# senzor.net
KiCad netlist of a schematic drawn in Altium Designer
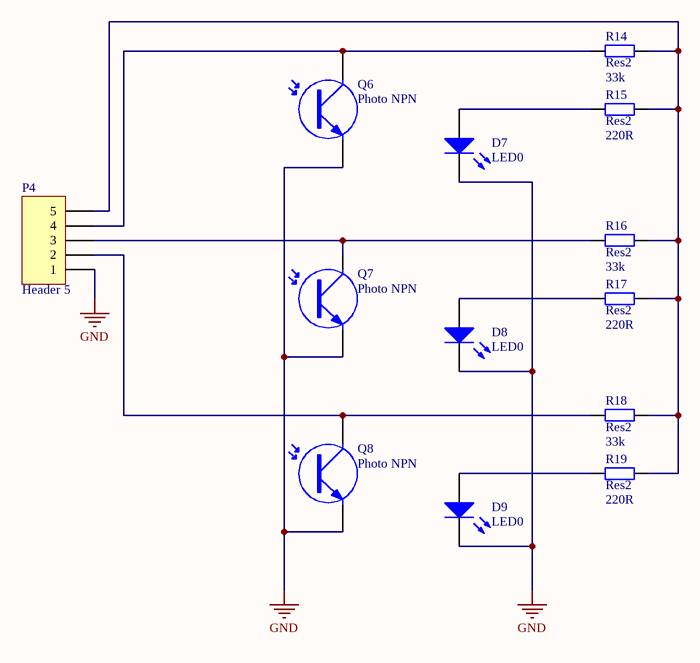
[diagram p0: senzor.SchDoc]

(export (version "E")
  (design (tool "Eeschema 10.0.6"))
  (components
    (comp (ref "D7")
      (value "LED0")
      (footprint "LED-0")
      (description "Typical INFRARED GaAs LED")
      (fields (field (name "PUBLISHER") "Altium Limited"))
      (libsource (lib "Miscellaneous Devices") (part "LED0"))
    )
    (comp (ref "D8")
      (value "LED0")
      (footprint "LED-0")
      (description "Typical INFRARED GaAs LED")
      (fields (field (name "PUBLISHER") "Altium Limited"))
      (libsource (lib "Miscellaneous Devices") (part "LED0"))
    )
    (comp (ref "D9")
      (value "LED0")
      (footprint "LED-0")
      (description "Typical INFRARED GaAs LED")
      (fields (field (name "PUBLISHER") "Altium Limited"))
      (libsource (lib "Miscellaneous Devices") (part "LED0"))
    )
    (comp (ref "P4")
      (value "Header 5")
      (footprint "HDR1X5")
      (description "Header, 5-Pin")
      (fields (field (name "PUBLISHER") "Altium Limited"))
      (libsource (lib "Miscellaneous Connectors") (part "Header 5"))
    )
    (comp (ref "Q6")
      (value "Photo NPN")
      (footprint "TO-220_A")
      (description "NPN Phototransistor")
      (fields (field (name "PUBLISHER") "Altium Limited"))
      (libsource (lib "Miscellaneous Devices") (part "Photo NPN"))
    )
    (comp (ref "Q7")
      (value "Photo NPN")
      (footprint "TO-220_A")
      (description "NPN Phototransistor")
      (fields (field (name "PUBLISHER") "Altium Limited"))
      (libsource (lib "Miscellaneous Devices") (part "Photo NPN"))
    )
    (comp (ref "Q8")
      (value "Photo NPN")
      (footprint "TO-220_A")
      (description "NPN Phototransistor")
      (fields (field (name "PUBLISHER") "Altium Limited"))
      (libsource (lib "Miscellaneous Devices") (part "Photo NPN"))
    )
    (comp (ref "R14")
      (value "Res2")
      (footprint "AXIAL-0.4")
      (description "Resistor")
      (fields (field (name "ALTIUM_VALUE") "33k") (field (name "PUBLISHER") "Altium Limited"))
      (libsource (lib "Miscellaneous Devices") (part "Res2"))
    )
    (comp (ref "R15")
      (value "Res2")
      (footprint "AXIAL-0.4")
      (description "Resistor")
      (fields (field (name "ALTIUM_VALUE") "220R") (field (name "PUBLISHER") "Altium Limited"))
      (libsource (lib "Miscellaneous Devices") (part "Res2"))
    )
    (comp (ref "R16")
      (value "Res2")
      (footprint "AXIAL-0.4")
      (description "Resistor")
      (fields (field (name "ALTIUM_VALUE") "33k") (field (name "PUBLISHER") "Altium Limited"))
      (libsource (lib "Miscellaneous Devices") (part "Res2"))
    )
    (comp (ref "R17")
      (value "Res2")
      (footprint "AXIAL-0.4")
      (description "Resistor")
      (fields (field (name "ALTIUM_VALUE") "220R") (field (name "PUBLISHER") "Altium Limited"))
      (libsource (lib "Miscellaneous Devices") (part "Res2"))
    )
    (comp (ref "R18")
      (value "Res2")
      (footprint "AXIAL-0.4")
      (description "Resistor")
      (fields (field (name "ALTIUM_VALUE") "33k") (field (name "PUBLISHER") "Altium Limited"))
      (libsource (lib "Miscellaneous Devices") (part "Res2"))
    )
    (comp (ref "R19")
      (value "Res2")
      (footprint "AXIAL-0.4")
      (description "Resistor")
      (fields (field (name "ALTIUM_VALUE") "220R") (field (name "PUBLISHER") "Altium Limited"))
      (libsource (lib "Miscellaneous Devices") (part "Res2"))
    )
  )
  (nets
    (net (code "1") (name "GND") (class "Default")
      (node (ref "D7") (pin "2") (pinfunction "K_2") (pintype "passive"))
      (node (ref "D8") (pin "2") (pinfunction "K_2") (pintype "passive"))
      (node (ref "D9") (pin "2") (pinfunction "K_2") (pintype "passive"))
      (node (ref "P4") (pin "1") (pinfunction "1_1") (pintype "passive"))
      (node (ref "Q6") (pin "3") (pinfunction "E_3") (pintype "passive"))
      (node (ref "Q7") (pin "3") (pinfunction "E_3") (pintype "passive"))
      (node (ref "Q8") (pin "3") (pinfunction "E_3") (pintype "passive"))
    )
    (net (code "2") (name "Net-(D7-A)") (class "Default")
      (node (ref "D7") (pin "1") (pinfunction "A_1") (pintype "passive"))
      (node (ref "R15") (pin "1") (pinfunction "1_1") (pintype "passive"))
    )
    (net (code "3") (name "Net-(D8-A)") (class "Default")
      (node (ref "D8") (pin "1") (pinfunction "A_1") (pintype "passive"))
      (node (ref "R17") (pin "1") (pinfunction "1_1") (pintype "passive"))
    )
    (net (code "4") (name "Net-(D9-A)") (class "Default")
      (node (ref "D9") (pin "1") (pinfunction "A_1") (pintype "passive"))
      (node (ref "R19") (pin "1") (pinfunction "1_1") (pintype "passive"))
    )
    (net (code "5") (name "Net-(P4-Pad5)") (class "Default")
      (node (ref "P4") (pin "5") (pinfunction "5_5") (pintype "passive"))
      (node (ref "R14") (pin "2") (pinfunction "2_2") (pintype "passive"))
      (node (ref "R15") (pin "2") (pinfunction "2_2") (pintype "passive"))
      (node (ref "R16") (pin "2") (pinfunction "2_2") (pintype "passive"))
      (node (ref "R17") (pin "2") (pinfunction "2_2") (pintype "passive"))
      (node (ref "R18") (pin "2") (pinfunction "2_2") (pintype "passive"))
      (node (ref "R19") (pin "2") (pinfunction "2_2") (pintype "passive"))
    )
    (net (code "6") (name "Net-(Q6-C)") (class "Default")
      (node (ref "P4") (pin "4") (pinfunction "4_4") (pintype "passive"))
      (node (ref "Q6") (pin "1") (pinfunction "C_1") (pintype "passive"))
      (node (ref "R14") (pin "1") (pinfunction "1_1") (pintype "passive"))
    )
    (net (code "7") (name "Net-(Q7-C)") (class "Default")
      (node (ref "P4") (pin "3") (pinfunction "3_3") (pintype "passive"))
      (node (ref "Q7") (pin "1") (pinfunction "C_1") (pintype "passive"))
      (node (ref "R16") (pin "1") (pinfunction "1_1") (pintype "passive"))
    )
    (net (code "8") (name "Net-(Q8-C)") (class "Default")
      (node (ref "P4") (pin "2") (pinfunction "2_2") (pintype "passive"))
      (node (ref "Q8") (pin "1") (pinfunction "C_1") (pintype "passive"))
      (node (ref "R18") (pin "1") (pinfunction "1_1") (pintype "passive"))
    )
  )
)
